# SCH_New-Project_2026-09-16.net
KiCad netlist of a schematic drawn in EasyEDA
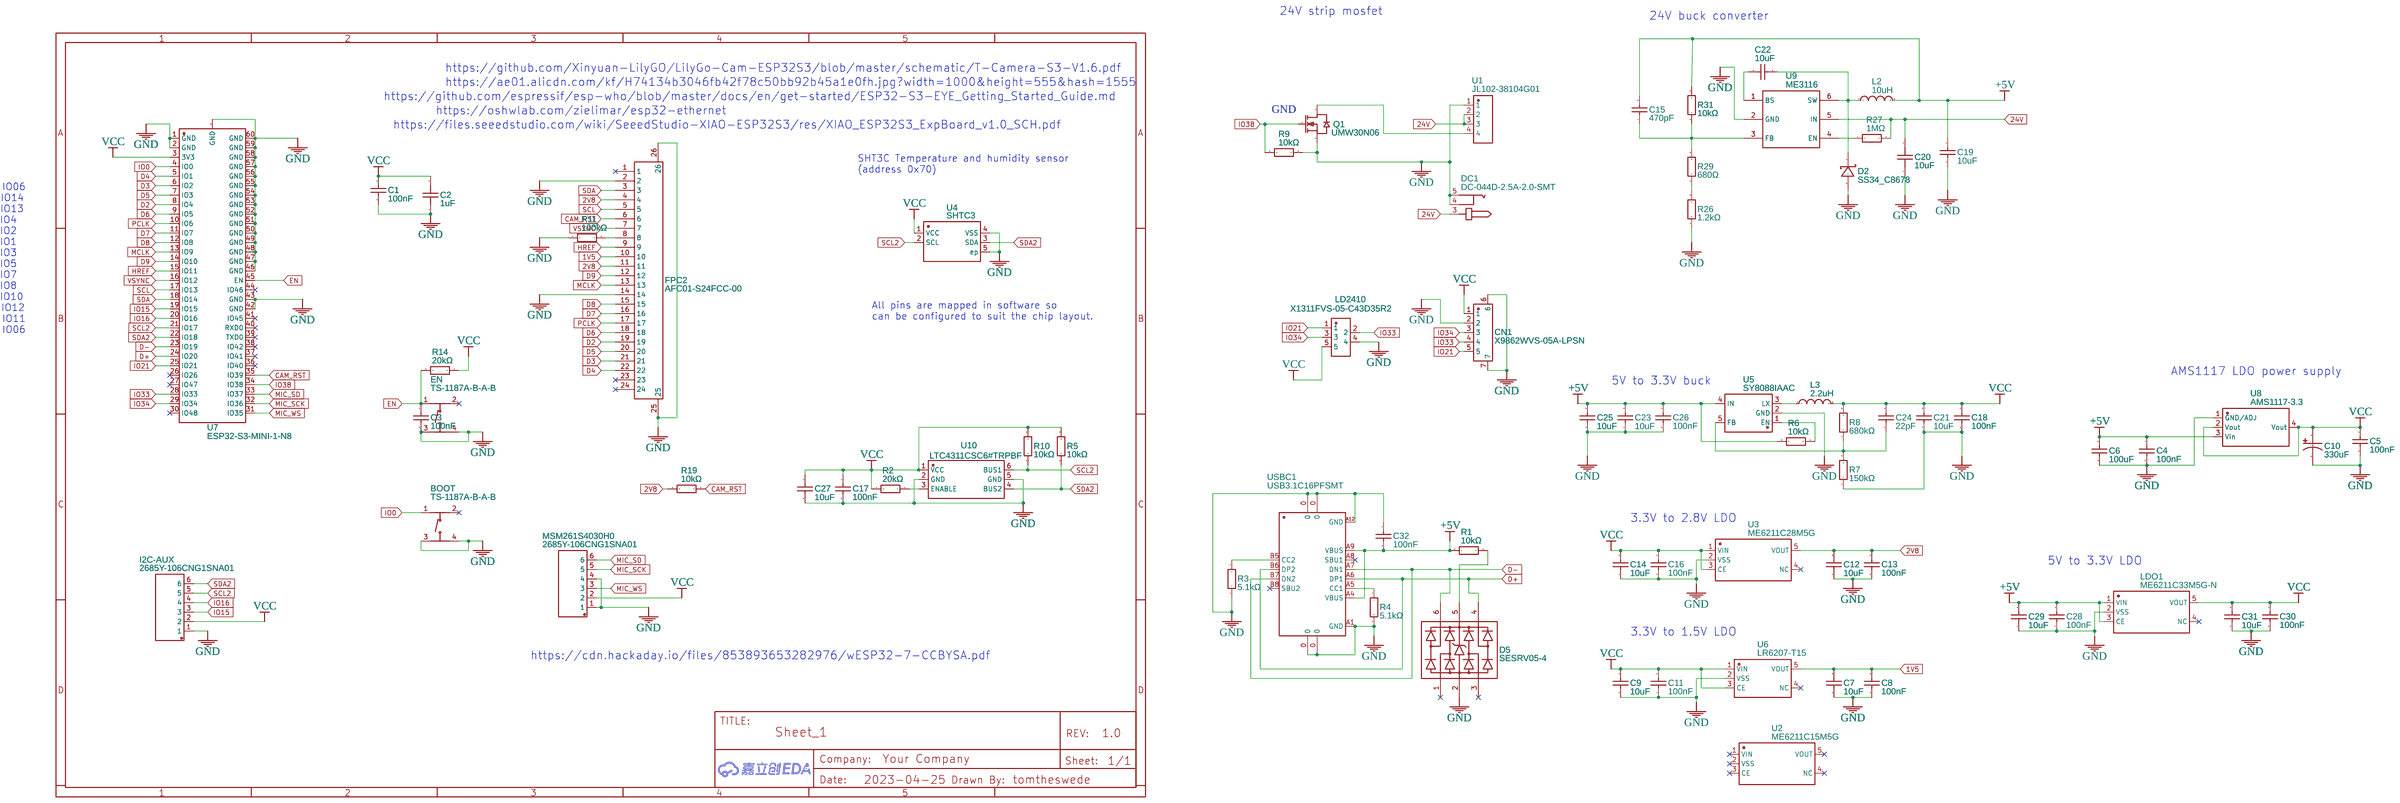
[diagram p0: schematic sheet]

(export (version "E")
  (design (tool "Eeschema 10.0.6"))
  (components
    (comp (ref "BOOT")
      (value "TS-1187A-B-A-B")
      (fields (field (name "Manufacturer") "XKB Enterprise"))
      (libsource (lib "") (part "TS-1187A-B-A-B_1"))
    )
    (comp (ref "C1")
      (value "100nF")
      (fields
        (field (name "Manufacturer Part") "CL05B104KO5NNNC")
        (field (name "Manufacturer") "SAMSUNG(三星)")
      )
      (libsource (lib "") (part "CL05B104KO5NNNC"))
    )
    (comp (ref "C2")
      (value "1uF")
      (fields
        (field (name "Manufacturer Part") "CL05A105KA5NQNC")
        (field (name "Manufacturer") "SAMSUNG(三星)")
      )
      (libsource (lib "") (part "CL05A105KA5NQNC"))
    )
    (comp (ref "C3")
      (value "100nF")
      (fields
        (field (name "Manufacturer Part") "CL05B104KO5NNNC")
        (field (name "Manufacturer") "SAMSUNG(三星)")
      )
      (libsource (lib "") (part "CL05B104KO5NNNC"))
    )
    (comp (ref "C4")
      (value "100nF")
      (fields
        (field (name "Manufacturer Part") "CL05B104KO5NNNC")
        (field (name "Manufacturer") "SAMSUNG(三星)")
      )
      (libsource (lib "") (part "CL05B104KO5NNNC"))
    )
    (comp (ref "C5")
      (value "100nF")
      (fields
        (field (name "Manufacturer Part") "CL05B104KO5NNNC")
        (field (name "Manufacturer") "SAMSUNG(三星)")
      )
      (libsource (lib "") (part "CL05B104KO5NNNC"))
    )
    (comp (ref "C6")
      (value "100uF")
      (fields (field (name "Manufacturer Part") "CL31A107MQHNNNE") (field (name "Manufacturer") "SAMSUNG"))
      (libsource (lib "") (part "CL31A107MQHNNNE"))
    )
    (comp (ref "C7")
      (value "10uF")
      (fields (field (name "Manufacturer Part") "CL05A106MQ5NUNC") (field (name "Manufacturer") "SAMSUNG"))
      (libsource (lib "") (part "CL05A106MQ5NUNC"))
    )
    (comp (ref "C8")
      (value "100nF")
      (fields
        (field (name "Manufacturer Part") "CL05B104KO5NNNC")
        (field (name "Manufacturer") "SAMSUNG(三星)")
      )
      (libsource (lib "") (part "CL05B104KO5NNNC"))
    )
    (comp (ref "C9")
      (value "10uF")
      (fields (field (name "Manufacturer Part") "CL05A106MQ5NUNC") (field (name "Manufacturer") "SAMSUNG"))
      (libsource (lib "") (part "CL05A106MQ5NUNC"))
    )
    (comp (ref "C10")
      (value "330uF")
      (fields
        (field (name "Manufacturer Part") "CA45-C6R3K337T")
        (field (name "Manufacturer") "Hunan Xiangyee in S&T")
      )
      (libsource (lib "") (part "CA45-C6R3K337T"))
    )
    (comp (ref "C11")
      (value "100nF")
      (fields
        (field (name "Manufacturer Part") "CL05B104KO5NNNC")
        (field (name "Manufacturer") "SAMSUNG(三星)")
      )
      (libsource (lib "") (part "CL05B104KO5NNNC"))
    )
    (comp (ref "C12")
      (value "10uF")
      (fields (field (name "Manufacturer Part") "CL05A106MQ5NUNC") (field (name "Manufacturer") "SAMSUNG"))
      (libsource (lib "") (part "CL05A106MQ5NUNC"))
    )
    (comp (ref "C13")
      (value "100nF")
      (fields
        (field (name "Manufacturer Part") "CL05B104KO5NNNC")
        (field (name "Manufacturer") "SAMSUNG(三星)")
      )
      (libsource (lib "") (part "CL05B104KO5NNNC"))
    )
    (comp (ref "C14")
      (value "10uF")
      (fields (field (name "Manufacturer Part") "CL05A106MQ5NUNC") (field (name "Manufacturer") "SAMSUNG"))
      (libsource (lib "") (part "CL05A106MQ5NUNC"))
    )
    (comp (ref "C15")
      (value "470pF")
      (fields (field (name "Manufacturer Part") "0402B471K500NT") (field (name "Manufacturer") "FH(风华)"))
      (libsource (lib "") (part "0402B471K500NT"))
    )
    (comp (ref "C16")
      (value "100nF")
      (fields
        (field (name "Manufacturer Part") "CL05B104KO5NNNC")
        (field (name "Manufacturer") "SAMSUNG(三星)")
      )
      (libsource (lib "") (part "CL05B104KO5NNNC"))
    )
    (comp (ref "C17")
      (value "100nF")
      (fields
        (field (name "Manufacturer Part") "CL05B104KO5NNNC")
        (field (name "Manufacturer") "SAMSUNG(三星)")
      )
      (libsource (lib "") (part "CL05B104KO5NNNC"))
    )
    (comp (ref "C18")
      (value "100nF")
      (fields
        (field (name "Manufacturer Part") "CL05B104KO5NNNC")
        (field (name "Manufacturer") "SAMSUNG(三星)")
      )
      (libsource (lib "") (part "CL05B104KO5NNNC"))
    )
    (comp (ref "C19")
      (value "10uF")
      (fields
        (field (name "Manufacturer Part") "CL21A106KAYNNNE")
        (field (name "Manufacturer") "SAMSUNG(三星)")
      )
      (libsource (lib "") (part "CL21A106KAYNNNE"))
    )
    (comp (ref "C20")
      (value "10uF")
      (fields
        (field (name "Manufacturer Part") "GRM21BR61H106KE43L")
        (field (name "Manufacturer") "muRata(村田)")
      )
      (libsource (lib "") (part "GRM21BR61H106KE43L"))
    )
    (comp (ref "C21")
      (value "10uF")
      (fields (field (name "Manufacturer Part") "CL05A106MQ5NUNC") (field (name "Manufacturer") "SAMSUNG"))
      (libsource (lib "") (part "CL05A106MQ5NUNC"))
    )
    (comp (ref "C22")
      (value "10uF")
      (fields
        (field (name "Manufacturer Part") "CL21A106KAYNNNE")
        (field (name "Manufacturer") "SAMSUNG(三星)")
      )
      (libsource (lib "") (part "CL21A106KAYNNNE_1"))
    )
    (comp (ref "C23")
      (value "10uF")
      (fields (field (name "Manufacturer Part") "CL05A106MQ5NUNC") (field (name "Manufacturer") "SAMSUNG"))
      (libsource (lib "") (part "CL05A106MQ5NUNC"))
    )
    (comp (ref "C24")
      (value "22pF")
      (fields (field (name "Manufacturer Part") "0402CG220J500NT") (field (name "Manufacturer") "FH(风华)"))
      (libsource (lib "") (part "0402CG220J500NT"))
    )
    (comp (ref "C25")
      (value "10uF")
      (fields (field (name "Manufacturer Part") "CL05A106MQ5NUNC") (field (name "Manufacturer") "SAMSUNG"))
      (libsource (lib "") (part "CL05A106MQ5NUNC"))
    )
    (comp (ref "C26")
      (value "100nF")
      (fields
        (field (name "Manufacturer Part") "CL05B104KO5NNNC")
        (field (name "Manufacturer") "SAMSUNG(三星)")
      )
      (libsource (lib "") (part "CL05B104KO5NNNC"))
    )
    (comp (ref "C27")
      (value "10uF")
      (fields (field (name "Manufacturer Part") "CL05A106MQ5NUNC") (field (name "Manufacturer") "SAMSUNG"))
      (libsource (lib "") (part "CL05A106MQ5NUNC"))
    )
    (comp (ref "C28")
      (value "100nF")
      (fields
        (field (name "Manufacturer Part") "CL05B104KO5NNNC")
        (field (name "Manufacturer") "SAMSUNG(三星)")
      )
      (libsource (lib "") (part "CL05B104KO5NNNC"))
    )
    (comp (ref "C29")
      (value "10uF")
      (fields (field (name "Manufacturer Part") "CL05A106MQ5NUNC") (field (name "Manufacturer") "SAMSUNG"))
      (libsource (lib "") (part "CL05A106MQ5NUNC"))
    )
    (comp (ref "C30")
      (value "100nF")
      (fields
        (field (name "Manufacturer Part") "CL05B104KO5NNNC")
        (field (name "Manufacturer") "SAMSUNG(三星)")
      )
      (libsource (lib "") (part "CL05B104KO5NNNC"))
    )
    (comp (ref "C31")
      (value "10uF")
      (fields (field (name "Manufacturer Part") "CL05A106MQ5NUNC") (field (name "Manufacturer") "SAMSUNG"))
      (libsource (lib "") (part "CL05A106MQ5NUNC"))
    )
    (comp (ref "C32")
      (value "100nF")
      (fields
        (field (name "Manufacturer Part") "CL05B104KO5NNNC")
        (field (name "Manufacturer") "SAMSUNG(三星)")
      )
      (libsource (lib "") (part "CL05B104KO5NNNC"))
    )
    (comp (ref "CN1")
      (value "X9862WVS-05A-LPSN")
      (fields
        (field (name "Manufacturer Part") "X9862WVS-05A-6TSN")
        (field (name "Manufacturer") "XKB Connectivity(中国星坤)")
      )
      (libsource (lib "") (part "X9862WVS-05A-LPSN"))
    )
    (comp (ref "D2")
      (value "SS34_C8678")
      (fields (field (name "Manufacturer Part") "SS34") (field (name "Manufacturer") "MDD"))
      (libsource (lib "") (part "SS34_C8678"))
    )
    (comp (ref "D5")
      (value "SESRV05-4")
      (fields (field (name "Manufacturer") "SEMIWARE(赛米微尔)"))
      (libsource (lib "") (part "SESRV05-4"))
    )
    (comp (ref "DC1")
      (value "DC-044D-2.5A-2.0-SMT")
      (fields (field (name "Manufacturer") "XKB Connectivity(中国星坤)"))
      (libsource (lib "") (part "DC-044D-2.5A-2.0-SMT"))
    )
    (comp (ref "EN")
      (value "TS-1187A-B-A-B")
      (fields (field (name "Manufacturer") "XKB Enterprise"))
      (libsource (lib "") (part "TS-1187A-B-A-B"))
    )
    (comp (ref "FPC2")
      (value "AFC01-S24FCC-00")
      (fields (field (name "Manufacturer") "JS(钜硕电子)"))
      (libsource (lib "") (part "AFC01-S24FCC-00"))
    )
    (comp (ref "I2C-AUX")
      (value "2685Y-106CNG1SNA01")
      (fields (field (name "Manufacturer") "华宇创"))
      (libsource (lib "") (part "2685Y-106CNG1SNA01_1"))
    )
    (comp (ref "L2")
      (value "10uH")
      (fields (field (name "Manufacturer Part") "SM5845-100MT") (field (name "Manufacturer") "SXN(顺翔诺)"))
      (libsource (lib "") (part "SM5845-100MT"))
    )
    (comp (ref "L3")
      (value "2.2uH")
      (fields (field (name "Manufacturer Part") "FNR4030S2R2MT") (field (name "Manufacturer") "cjiang(长江微电)"))
      (libsource (lib "") (part "FNR4030S2R2MT"))
    )
    (comp (ref "LD2410")
      (value "X1311FVS-05-C43D35R2")
      (fields (field (name "Manufacturer") "XKB Connectivity(中国星坤)"))
      (libsource (lib "") (part "X1311FVS-05-C43D35R2"))
    )
    (comp (ref "LDO1")
      (value "ME6211C33M5G-N")
      (fields (field (name "Manufacturer") "MICRONE(南京微盟)"))
      (libsource (lib "") (part "ME6211C33M5G-N"))
    )
    (comp (ref "MSM261S4030H0")
      (value "2685Y-106CNG1SNA01")
      (fields (field (name "Manufacturer") "华宇创"))
      (libsource (lib "") (part "2685Y-106CNG1SNA01"))
    )
    (comp (ref "Q1")
      (value "UMW30N06")
      (fields (field (name "Manufacturer Part") "30N06") (field (name "Manufacturer") "UMW(广东友台半导体)"))
      (libsource (lib "") (part "UMW30N06"))
    )
    (comp (ref "R1")
      (value "10kΩ")
      (fields (field (name "Manufacturer Part") "0402WGF1002TCE") (field (name "Manufacturer") "UniOhm"))
      (libsource (lib "") (part "0402WGF1002TCE"))
    )
    (comp (ref "R2")
      (value "20kΩ")
      (fields
        (field (name "Manufacturer Part") "0402WGF2002TCE")
        (field (name "Manufacturer") "UNI-ROYAL(厚声)")
      )
      (libsource (lib "") (part "0402WGF2002TCE"))
    )
    (comp (ref "R3")
      (value "5.1kΩ")
      (fields (field (name "Manufacturer Part") "0402WGF5101TCE") (field (name "Manufacturer") "UniOhm"))
      (libsource (lib "") (part "0402WGF5101TCE"))
    )
    (comp (ref "R4")
      (value "5.1kΩ")
      (fields (field (name "Manufacturer Part") "0402WGF5101TCE") (field (name "Manufacturer") "UniOhm"))
      (libsource (lib "") (part "0402WGF5101TCE_1"))
    )
    (comp (ref "R5")
      (value "10kΩ")
      (fields (field (name "Manufacturer Part") "0402WGF1002TCE") (field (name "Manufacturer") "UniOhm"))
      (libsource (lib "") (part "0402WGF1002TCE_1"))
    )
    (comp (ref "R6")
      (value "10kΩ")
      (fields (field (name "Manufacturer Part") "0402WGF1002TCE") (field (name "Manufacturer") "UniOhm"))
      (libsource (lib "") (part "0402WGF1002TCE"))
    )
    (comp (ref "R7")
      (value "150kΩ")
      (fields
        (field (name "Manufacturer Part") "0402WGF1503TCE")
        (field (name "Manufacturer") "UNI-ROYAL(厚声)")
      )
      (libsource (lib "") (part "0402WGF1503TCE"))
    )
    (comp (ref "R8")
      (value "680kΩ")
      (fields
        (field (name "Manufacturer Part") "0603WAF6803T5E")
        (field (name "Manufacturer") "UNI-ROYAL(厚声)")
      )
      (libsource (lib "") (part "0603WAF6803T5E"))
    )
    (comp (ref "R9")
      (value "10kΩ")
      (fields (field (name "Manufacturer Part") "0402WGF1002TCE") (field (name "Manufacturer") "UniOhm"))
      (libsource (lib "") (part "0402WGF1002TCE_2"))
    )
    (comp (ref "R10")
      (value "10kΩ")
      (fields (field (name "Manufacturer Part") "0402WGF1002TCE") (field (name "Manufacturer") "UniOhm"))
      (libsource (lib "") (part "0402WGF1002TCE_1"))
    )
    (comp (ref "R11")
      (value "100kΩ")
      (fields
        (field (name "Manufacturer Part") "0402WGF1003TCE")
        (field (name "Manufacturer") "UNI-ROYAL(厚声)")
      )
      (libsource (lib "") (part "0402WGF1003TCE"))
    )
    (comp (ref "R14")
      (value "20kΩ")
      (fields
        (field (name "Manufacturer Part") "0402WGF2002TCE")
        (field (name "Manufacturer") "UNI-ROYAL(厚声)")
      )
      (libsource (lib "") (part "0402WGF2002TCE"))
    )
    (comp (ref "R19")
      (value "10kΩ")
      (fields (field (name "Manufacturer Part") "0402WGF1002TCE") (field (name "Manufacturer") "UniOhm"))
      (libsource (lib "") (part "0402WGF1002TCE_2"))
    )
    (comp (ref "R26")
      (value "1.2kΩ")
      (fields
        (field (name "Manufacturer Part") "0402WGF1201TCE")
        (field (name "Manufacturer") "UNI-ROYAL(厚声)")
      )
      (libsource (lib "") (part "0402WGF1201TCE"))
    )
    (comp (ref "R27")
      (value "1MΩ")
      (fields
        (field (name "Manufacturer Part") "0805W8F1004T5E")
        (field (name "Manufacturer") "UNI-ROYAL(厚声)")
      )
      (libsource (lib "") (part "0805W8F1004T5E"))
    )
    (comp (ref "R29")
      (value "680Ω")
      (fields
        (field (name "Manufacturer Part") "0402WGF6800TCE")
        (field (name "Manufacturer") "UNI-ROYAL(厚声)")
      )
      (libsource (lib "") (part "0402WGF6800TCE"))
    )
    (comp (ref "R31")
      (value "10kΩ")
      (fields (field (name "Manufacturer Part") "0402WGF1002TCE") (field (name "Manufacturer") "UniOhm"))
      (libsource (lib "") (part "0402WGF1002TCE_1"))
    )
    (comp (ref "U1")
      (value "JL102-38104G01")
      (fields (field (name "Manufacturer") "JILN(锦凌)"))
      (libsource (lib "") (part "JL102-38104G01"))
    )
    (comp (ref "U2")
      (value "ME6211C15M5G")
      (fields
        (field (name "Manufacturer Part") "ME6211C15M5G-N")
        (field (name "Manufacturer") "MICRONE(南京微盟)")
      )
      (libsource (lib "") (part "ME6211C15M5G"))
    )
    (comp (ref "U3")
      (value "ME6211C28M5G")
      (fields
        (field (name "Manufacturer Part") "ME6211C28M5G-N")
        (field (name "Manufacturer") "MICRONE(南京微盟)")
      )
      (libsource (lib "") (part "ME6211C28M5G"))
    )
    (comp (ref "U4")
      (value "SHTC3")
      (fields (field (name "Manufacturer") "Sensirion"))
      (libsource (lib "") (part "SHTC3"))
    )
    (comp (ref "U5")
      (value "SY8088IAAC")
      (fields (field (name "Manufacturer") "矽力杰silergy"))
      (libsource (lib "") (part "SY8088IAAC"))
    )
    (comp (ref "U6")
      (value "LR6207-T15")
      (fields (field (name "Manufacturer") "LR(朗瑞)"))
      (libsource (lib "") (part "LR6207-T15"))
    )
    (comp (ref "U7")
      (value "ESP32-S3-MINI-1-N8")
      (fields (field (name "Manufacturer") "ESPRESSIF(乐鑫)"))
      (libsource (lib "") (part "ESP32-S3-MINI-1-N8"))
    )
    (comp (ref "U8")
      (value "AMS1117-3.3")
      (fields (field (name "Manufacturer") "AMS"))
      (libsource (lib "") (part "AMS1117-3.3"))
    )
    (comp (ref "U9")
      (value "ME3116")
      (fields (field (name "Manufacturer Part") "ME3116AM6G") (field (name "Manufacturer") "MICRONE(南京微盟)"))
      (libsource (lib "") (part "ME3116"))
    )
    (comp (ref "U10")
      (value "LTC4311CSC6#TRPBF")
      (fields (field (name "Manufacturer") "ADI(亚德诺)"))
      (libsource (lib "") (part "LTC4311CSC6#TRPBF"))
    )
    (comp (ref "USBC1")
      (value "USB3.1C16PFSMT")
      (fields (field (name "Manufacturer") "LCSC"))
      (libsource (lib "") (part "USB3.1C16PFSMT"))
    )
  )
  (nets
    (net (code "1") (name "+5V") (class "Default")
      (node (ref "C15") (pin "2") (pinfunction "2_2") (pintype "input"))
      (node (ref "C19") (pin "2") (pinfunction "2_2") (pintype "input"))
      (node (ref "C23") (pin "2") (pinfunction "2_2") (pintype "input"))
      (node (ref "C25") (pin "2") (pinfunction "2_2") (pintype "input"))
      (node (ref "C26") (pin "1") (pinfunction "1_1") (pintype "input"))
      (node (ref "C28") (pin "1") (pinfunction "1_1") (pintype "input"))
      (node (ref "C29") (pin "2") (pinfunction "2_2") (pintype "input"))
      (node (ref "C32") (pin "2") (pinfunction "2_2") (pintype "input"))
      (node (ref "C4") (pin "1") (pinfunction "1_1") (pintype "input"))
      (node (ref "C6") (pin "1") (pinfunction "1_1") (pintype "input"))
      (node (ref "L2") (pin "2") (pinfunction "2_2") (pintype "unspecified"))
      (node (ref "LDO1") (pin "1") (pinfunction "VIN_1") (pintype "unspecified"))
      (node (ref "LDO1") (pin "3") (pinfunction "CE_3") (pintype "unspecified"))
      (node (ref "R1") (pin "2") (pinfunction "2_2") (pintype "input"))
      (node (ref "R31") (pin "2") (pinfunction "2_2") (pintype "input"))
      (node (ref "R6") (pin "2") (pinfunction "2_2") (pintype "input"))
      (node (ref "U5") (pin "4") (pinfunction "IN_4") (pintype "unspecified"))
      (node (ref "U8") (pin "3") (pinfunction "Vin_3") (pintype "unspecified"))
      (node (ref "USBC1") (pin "A4") (pinfunction "VBUS_A4") (pintype "unspecified"))
      (node (ref "USBC1") (pin "A9") (pinfunction "VBUS_A9") (pintype "unspecified"))
    )
    (net (code "2") (name "1V5") (class "Default")
      (node (ref "C7") (pin "2") (pinfunction "2_2") (pintype "input"))
      (node (ref "C8") (pin "1") (pinfunction "1_1") (pintype "input"))
      (node (ref "FPC2") (pin "10") (pinfunction "10_10") (pintype "unspecified"))
      (node (ref "U6") (pin "5") (pinfunction "VOUT_5") (pintype "unspecified"))
    )
    (net (code "3") (name "2V8") (class "Default")
      (node (ref "C12") (pin "2") (pinfunction "2_2") (pintype "input"))
      (node (ref "C13") (pin "1") (pinfunction "1_1") (pintype "input"))
      (node (ref "FPC2") (pin "11") (pinfunction "11_11") (pintype "unspecified"))
      (node (ref "FPC2") (pin "4") (pinfunction "4_4") (pintype "unspecified"))
      (node (ref "R19") (pin "1") (pinfunction "1_1") (pintype "input"))
      (node (ref "U3") (pin "5") (pinfunction "VOUT_5") (pintype "unspecified"))
    )
    (net (code "4") (name "24V") (class "Default")
      (node (ref "C20") (pin "2") (pinfunction "2_2") (pintype "unspecified"))
      (node (ref "DC1") (pin "3") (pinfunction "3_3") (pintype "unspecified"))
      (node (ref "R27") (pin "2") (pinfunction "2_2") (pintype "input"))
      (node (ref "U1") (pin "2") (pinfunction "2_2") (pintype "unspecified"))
      (node (ref "U1") (pin "3") (pinfunction "3_3") (pintype "unspecified"))
      (node (ref "U9") (pin "5") (pinfunction "IN_5") (pintype "unspecified"))
    )
    (net (code "5") (name "CAM_RST") (class "Default")
      (node (ref "FPC2") (pin "6") (pinfunction "6_6") (pintype "unspecified"))
      (node (ref "R19") (pin "2") (pinfunction "2_2") (pintype "input"))
      (node (ref "U7") (pin "35") (pinfunction "IO39_35") (pintype "unspecified"))
    )
    (net (code "6") (name "D+") (class "Default")
      (node (ref "D5") (pin "4") (pinfunction "4_4") (pintype "unspecified"))
      (node (ref "U7") (pin "24") (pinfunction "IO20_24") (pintype "unspecified"))
      (node (ref "USBC1") (pin "A6") (pinfunction "DP1_A6") (pintype "unspecified"))
      (node (ref "USBC1") (pin "B6") (pinfunction "DP2_B6") (pintype "unspecified"))
    )
    (net (code "7") (name "D-") (class "Default")
      (node (ref "D5") (pin "6") (pinfunction "6_6") (pintype "unspecified"))
      (node (ref "U7") (pin "23") (pinfunction "IO19_23") (pintype "unspecified"))
      (node (ref "USBC1") (pin "A7") (pinfunction "DN1_A7") (pintype "unspecified"))
      (node (ref "USBC1") (pin "B7") (pinfunction "DN2_B7") (pintype "unspecified"))
    )
    (net (code "8") (name "D2") (class "Default")
      (node (ref "FPC2") (pin "19") (pinfunction "19_19") (pintype "unspecified"))
      (node (ref "U7") (pin "8") (pinfunction "IO4_8") (pintype "unspecified"))
    )
    (net (code "9") (name "D3") (class "Default")
      (node (ref "FPC2") (pin "21") (pinfunction "21_21") (pintype "unspecified"))
      (node (ref "U7") (pin "6") (pinfunction "IO2_6") (pintype "unspecified"))
    )
    (net (code "10") (name "D4") (class "Default")
      (node (ref "FPC2") (pin "22") (pinfunction "22_22") (pintype "unspecified"))
      (node (ref "U7") (pin "5") (pinfunction "IO1_5") (pintype "unspecified"))
    )
    (net (code "11") (name "D5") (class "Default")
      (node (ref "FPC2") (pin "20") (pinfunction "20_20") (pintype "unspecified"))
      (node (ref "U7") (pin "7") (pinfunction "IO3_7") (pintype "unspecified"))
    )
    (net (code "12") (name "D6") (class "Default")
      (node (ref "FPC2") (pin "18") (pinfunction "18_18") (pintype "unspecified"))
      (node (ref "U7") (pin "9") (pinfunction "IO5_9") (pintype "unspecified"))
    )
    (net (code "13") (name "D7") (class "Default")
      (node (ref "FPC2") (pin "16") (pinfunction "16_16") (pintype "unspecified"))
      (node (ref "U7") (pin "11") (pinfunction "IO7_11") (pintype "unspecified"))
    )
    (net (code "14") (name "D8") (class "Default")
      (node (ref "FPC2") (pin "15") (pinfunction "15_15") (pintype "unspecified"))
      (node (ref "U7") (pin "12") (pinfunction "IO8_12") (pintype "unspecified"))
    )
    (net (code "15") (name "D9") (class "Default")
      (node (ref "FPC2") (pin "12") (pinfunction "12_12") (pintype "unspecified"))
      (node (ref "U7") (pin "14") (pinfunction "IO10_14") (pintype "unspecified"))
    )
    (net (code "16") (name "EN") (class "Default")
      (node (ref "C3") (pin "1") (pinfunction "1_1") (pintype "input"))
      (node (ref "EN") (pin "1") (pinfunction "A_1") (pintype "unspecified"))
      (node (ref "R14") (pin "2") (pinfunction "2_2") (pintype "input"))
      (node (ref "U7") (pin "45") (pinfunction "EN_45") (pintype "unspecified"))
    )
    (net (code "17") (name "GND") (class "Default")
      (node (ref "BOOT") (pin "3") (pinfunction "C_3") (pintype "unspecified"))
      (node (ref "BOOT") (pin "4") (pinfunction "D_4") (pintype "unspecified"))
      (node (ref "C1") (pin "2") (pinfunction "2_2") (pintype "input"))
      (node (ref "C10") (pin "2") (pinfunction "2_2") (pintype "unspecified"))
      (node (ref "C11") (pin "2") (pinfunction "2_2") (pintype "input"))
      (node (ref "C12") (pin "1") (pinfunction "1_1") (pintype "input"))
      (node (ref "C13") (pin "2") (pinfunction "2_2") (pintype "input"))
      (node (ref "C14") (pin "1") (pinfunction "1_1") (pintype "input"))
      (node (ref "C16") (pin "2") (pinfunction "2_2") (pintype "input"))
      (node (ref "C17") (pin "2") (pinfunction "2_2") (pintype "input"))
      (node (ref "C18") (pin "2") (pinfunction "2_2") (pintype "input"))
      (node (ref "C19") (pin "1") (pinfunction "1_1") (pintype "input"))
      (node (ref "C2") (pin "1") (pinfunction "1_1") (pintype "unspecified"))
      (node (ref "C20") (pin "1") (pinfunction "1_1") (pintype "unspecified"))
      (node (ref "C21") (pin "1") (pinfunction "1_1") (pintype "input"))
      (node (ref "C23") (pin "1") (pinfunction "1_1") (pintype "input"))
      (node (ref "C25") (pin "1") (pinfunction "1_1") (pintype "input"))
      (node (ref "C26") (pin "2") (pinfunction "2_2") (pintype "input"))
      (node (ref "C27") (pin "1") (pinfunction "1_1") (pintype "input"))
      (node (ref "C28") (pin "2") (pinfunction "2_2") (pintype "input"))
      (node (ref "C29") (pin "1") (pinfunction "1_1") (pintype "input"))
      (node (ref "C3") (pin "2") (pinfunction "2_2") (pintype "input"))
      (node (ref "C30") (pin "2") (pinfunction "2_2") (pintype "input"))
      (node (ref "C31") (pin "1") (pinfunction "1_1") (pintype "input"))
      (node (ref "C32") (pin "1") (pinfunction "1_1") (pintype "input"))
      (node (ref "C4") (pin "2") (pinfunction "2_2") (pintype "input"))
      (node (ref "C5") (pin "2") (pinfunction "2_2") (pintype "input"))
      (node (ref "C6") (pin "2") (pinfunction "2_2") (pintype "input"))
      (node (ref "C7") (pin "1") (pinfunction "1_1") (pintype "input"))
      (node (ref "C8") (pin "2") (pinfunction "2_2") (pintype "input"))
      (node (ref "C9") (pin "1") (pinfunction "1_1") (pintype "input"))
      (node (ref "CN1") (pin "2") (pinfunction "2_2") (pintype "unspecified"))
      (node (ref "CN1") (pin "6") (pinfunction "6_6") (pintype "unspecified"))
      (node (ref "CN1") (pin "7") (pinfunction "7_7") (pintype "unspecified"))
      (node (ref "D2") (pin "2") (pinfunction "A_2") (pintype "unspecified"))
      (node (ref "D5") (pin "2") (pinfunction "2_2") (pintype "unspecified"))
      (node (ref "DC1") (pin "4") (pinfunction "4_4") (pintype "unspecified"))
      (node (ref "DC1") (pin "5") (pinfunction "5_5") (pintype "unspecified"))
      (node (ref "EN") (pin "3") (pinfunction "C_3") (pintype "unspecified"))
      (node (ref "EN") (pin "4") (pinfunction "D_4") (pintype "unspecified"))
      (node (ref "FPC2") (pin "14") (pinfunction "14_14") (pintype "unspecified"))
      (node (ref "FPC2") (pin "2") (pinfunction "2_2") (pintype "unspecified"))
      (node (ref "FPC2") (pin "25") (pinfunction "25_25") (pintype "unspecified"))
      (node (ref "FPC2") (pin "26") (pinfunction "26_26") (pintype "unspecified"))
      (node (ref "I2C-AUX") (pin "1") (pinfunction "1_1") (pintype "unspecified"))
      (node (ref "LD2410") (pin "4") (pinfunction "4_4") (pintype "unspecified"))
      (node (ref "LDO1") (pin "2") (pinfunction "VSS_2") (pintype "unspecified"))
      (node (ref "MSM261S4030H0") (pin "1") (pinfunction "1_1") (pintype "unspecified"))
      (node (ref "MSM261S4030H0") (pin "4") (pinfunction "4_4") (pintype "unspecified"))
      (node (ref "Q1") (pin "3") (pinfunction "S_3") (pintype "unspecified"))
      (node (ref "R11") (pin "1") (pinfunction "1_1") (pintype "input"))
      (node (ref "R26") (pin "1") (pinfunction "1_1") (pintype "input"))
      (node (ref "R3") (pin "1") (pinfunction "1_1") (pintype "input"))
      (node (ref "R4") (pin "2") (pinfunction "2_2") (pintype "input"))
      (node (ref "R7") (pin "1") (pinfunction "1_1") (pintype "input"))
      (node (ref "R9") (pin "2") (pinfunction "2_2") (pintype "input"))
      (node (ref "U1") (pin "1") (pinfunction "1_1") (pintype "unspecified"))
      (node (ref "U10") (pin "2") (pinfunction "GND_2") (pintype "unspecified"))
      (node (ref "U10") (pin "5") (pinfunction "GND_5") (pintype "unspecified"))
      (node (ref "U3") (pin "2") (pinfunction "VSS_2") (pintype "unspecified"))
      (node (ref "U4") (pin "4") (pinfunction "VSS_4") (pintype "unspecified"))
      (node (ref "U4") (pin "5") (pinfunction "ep_5") (pintype "unspecified"))
      (node (ref "U5") (pin "2") (pinfunction "GND_2") (pintype "unspecified"))
      (node (ref "U6") (pin "2") (pinfunction "VSS_2") (pintype "unspecified"))
      (node (ref "U7") (pin "1") (pinfunction "GND_1") (pintype "unspecified"))
      (node (ref "U7") (pin "2") (pinfunction "GND_2") (pintype "unspecified"))
      (node (ref "U7") (pin "42") (pinfunction "GND_42") (pintype "unspecified"))
      (node (ref "U7") (pin "43") (pinfunction "GND_43") (pintype "unspecified"))
      (node (ref "U7") (pin "46") (pinfunction "GND_46") (pintype "unspecified"))
      (node (ref "U7") (pin "47") (pinfunction "GND_47") (pintype "unspecified"))
      (node (ref "U7") (pin "48") (pinfunction "GND_48") (pintype "unspecified"))
      (node (ref "U7") (pin "49") (pinfunction "GND_49") (pintype "unspecified"))
      (node (ref "U7") (pin "50") (pinfunction "GND_50") (pintype "unspecified"))
      (node (ref "U7") (pin "51") (pinfunction "GND_51") (pintype "unspecified"))
      (node (ref "U7") (pin "52") (pinfunction "GND_52") (pintype "unspecified"))
      (node (ref "U7") (pin "53") (pinfunction "GND_53") (pintype "unspecified"))
      (node (ref "U7") (pin "54") (pinfunction "GND_54") (pintype "unspecified"))
      (node (ref "U7") (pin "55") (pinfunction "GND_55") (pintype "unspecified"))
      (node (ref "U7") (pin "56") (pinfunction "GND_56") (pintype "unspecified"))
      (node (ref "U7") (pin "57") (pinfunction "GND_57") (pintype "unspecified"))
      (node (ref "U7") (pin "58") (pinfunction "GND_58") (pintype "unspecified"))
      (node (ref "U7") (pin "59") (pinfunction "GND_59") (pintype "unspecified"))
      (node (ref "U7") (pin "60") (pinfunction "GND_60") (pintype "unspecified"))
      (node (ref "U7") (pin "GND") (pinfunction "GND_GND") (pintype "unspecified"))
      (node (ref "U8") (pin "1") (pinfunction "GND/ADJ_1") (pintype "unspecified"))
      (node (ref "U9") (pin "2") (pinfunction "GND_2") (pintype "unspecified"))
      (node (ref "USBC1") (pin "0") (pinfunction "0_0") (pintype "unspecified"))
      (node (ref "USBC1") (pin "A1") (pinfunction "GND_A1") (pintype "unspecified"))
      (node (ref "USBC1") (pin "A12") (pinfunction "GND_A12") (pintype "unspecified"))
    )
    (net (code "18") (name "HREF") (class "Default")
      (node (ref "FPC2") (pin "9") (pinfunction "9_9") (pintype "unspecified"))
      (node (ref "U7") (pin "15") (pinfunction "IO11_15") (pintype "unspecified"))
    )
    (net (code "19") (name "IO0") (class "Default")
      (node (ref "BOOT") (pin "1") (pinfunction "A_1") (pintype "unspecified"))
      (node (ref "U7") (pin "4") (pinfunction "IO0_4") (pintype "unspecified"))
    )
    (net (code "20") (name "IO15") (class "Default")
      (node (ref "I2C-AUX") (pin "3") (pinfunction "3_3") (pintype "unspecified"))
      (node (ref "U7") (pin "19") (pinfunction "IO15_19") (pintype "unspecified"))
    )
    (net (code "21") (name "IO16") (class "Default")
      (node (ref "I2C-AUX") (pin "4") (pinfunction "4_4") (pintype "unspecified"))
      (node (ref "U7") (pin "20") (pinfunction "IO16_20") (pintype "unspecified"))
    )
    (net (code "22") (name "IO21") (class "Default")
      (node (ref "CN1") (pin "5") (pinfunction "5_5") (pintype "unspecified"))
      (node (ref "LD2410") (pin "1") (pinfunction "1_1") (pintype "unspecified"))
      (node (ref "U7") (pin "25") (pinfunction "IO21_25") (pintype "unspecified"))
    )
    (net (code "23") (name "IO33") (class "Default")
      (node (ref "CN1") (pin "4") (pinfunction "4_4") (pintype "unspecified"))
      (node (ref "LD2410") (pin "2") (pinfunction "2_2") (pintype "unspecified"))
      (node (ref "U7") (pin "28") (pinfunction "IO33_28") (pintype "unspecified"))
    )
    (net (code "24") (name "IO34") (class "Default")
      (node (ref "CN1") (pin "3") (pinfunction "3_3") (pintype "unspecified"))
      (node (ref "LD2410") (pin "3") (pinfunction "3_3") (pintype "unspecified"))
      (node (ref "U7") (pin "29") (pinfunction "IO34_29") (pintype "unspecified"))
    )
    (net (code "25") (name "IO38") (class "Default")
      (node (ref "Q1") (pin "1") (pinfunction "G_1") (pintype "unspecified"))
      (node (ref "R9") (pin "1") (pinfunction "1_1") (pintype "input"))
      (node (ref "U7") (pin "34") (pinfunction "IO38_34") (pintype "unspecified"))
    )
    (net (code "26") (name "MCLK") (class "Default")
      (node (ref "FPC2") (pin "13") (pinfunction "13_13") (pintype "unspecified"))
      (node (ref "U7") (pin "13") (pinfunction "IO9_13") (pintype "unspecified"))
    )
    (net (code "27") (name "MIC_SCK") (class "Default")
      (node (ref "MSM261S4030H0") (pin "5") (pinfunction "5_5") (pintype "unspecified"))
      (node (ref "U7") (pin "32") (pinfunction "IO36_32") (pintype "unspecified"))
    )
    (net (code "28") (name "MIC_SD") (class "Default")
      (node (ref "MSM261S4030H0") (pin "6") (pinfunction "6_6") (pintype "unspecified"))
      (node (ref "U7") (pin "33") (pinfunction "IO37_33") (pintype "unspecified"))
    )
    (net (code "29") (name "MIC_WS") (class "Default")
      (node (ref "MSM261S4030H0") (pin "3") (pinfunction "3_3") (pintype "unspecified"))
      (node (ref "U7") (pin "31") (pinfunction "IO35_31") (pintype "unspecified"))
    )
    (net (code "30") (name "Net-(D2-K)") (class "Default")
      (node (ref "C22") (pin "1") (pinfunction "1_1") (pintype "input"))
      (node (ref "D2") (pin "1") (pinfunction "K_1") (pintype "unspecified"))
      (node (ref "L2") (pin "1") (pinfunction "1_1") (pintype "unspecified"))
      (node (ref "U9") (pin "6") (pinfunction "SW_6") (pintype "unspecified"))
    )
    (net (code "31") (name "Net-(D5-Pad5)") (class "Default")
      (node (ref "D5") (pin "5") (pinfunction "5_5") (pintype "unspecified"))
      (node (ref "R1") (pin "1") (pinfunction "1_1") (pintype "input"))
    )
    (net (code "32") (name "Net-(FPC2-Pad8)") (class "Default")
      (node (ref "FPC2") (pin "8") (pinfunction "8_8") (pintype "unspecified"))
      (node (ref "R11") (pin "2") (pinfunction "2_2") (pintype "input"))
    )
    (net (code "33") (name "Net-(Q1-D)") (class "Default")
      (node (ref "Q1") (pin "2") (pinfunction "D_2") (pintype "unspecified"))
      (node (ref "U1") (pin "4") (pinfunction "4_4") (pintype "unspecified"))
    )
    (net (code "34") (name "Net-(R26-Pad2)") (class "Default")
      (node (ref "R26") (pin "2") (pinfunction "2_2") (pintype "input"))
      (node (ref "R29") (pin "1") (pinfunction "1_1") (pintype "input"))
    )
    (net (code "35") (name "Net-(U5-EN)") (class "Default")
      (node (ref "R6") (pin "1") (pinfunction "1_1") (pintype "input"))
      (node (ref "U5") (pin "1") (pinfunction "EN_1") (pintype "unspecified"))
    )
    (net (code "36") (name "Net-(U5-FB)") (class "Default")
      (node (ref "C24") (pin "1") (pinfunction "1_1") (pintype "input"))
      (node (ref "R7") (pin "2") (pinfunction "2_2") (pintype "input"))
      (node (ref "R8") (pin "1") (pinfunction "1_1") (pintype "input"))
      (node (ref "U5") (pin "5") (pinfunction "FB_5") (pintype "unspecified"))
    )
    (net (code "37") (name "Net-(U5-LX)") (class "Default")
      (node (ref "L3") (pin "1") (pinfunction "1_1") (pintype "unspecified"))
      (node (ref "U5") (pin "3") (pinfunction "LX_3") (pintype "unspecified"))
    )
    (net (code "38") (name "Net-(U9-BS)") (class "Default")
      (node (ref "C22") (pin "2") (pinfunction "2_2") (pintype "input"))
      (node (ref "U9") (pin "1") (pinfunction "BS_1") (pintype "unspecified"))
    )
    (net (code "39") (name "Net-(U9-EN)") (class "Default")
      (node (ref "R27") (pin "1") (pinfunction "1_1") (pintype "input"))
      (node (ref "U9") (pin "4") (pinfunction "EN_4") (pintype "unspecified"))
    )
    (net (code "40") (name "Net-(U9-FB)") (class "Default")
      (node (ref "C15") (pin "1") (pinfunction "1_1") (pintype "input"))
      (node (ref "R29") (pin "2") (pinfunction "2_2") (pintype "input"))
      (node (ref "R31") (pin "1") (pinfunction "1_1") (pintype "input"))
      (node (ref "U9") (pin "3") (pinfunction "FB_3") (pintype "unspecified"))
    )
    (net (code "41") (name "Net-(U10-ENABLE)") (class "Default")
      (node (ref "R2") (pin "1") (pinfunction "1_1") (pintype "input"))
      (node (ref "U10") (pin "3") (pinfunction "ENABLE_3") (pintype "unspecified"))
    )
    (net (code "42") (name "Net-(USBC1-CC1)") (class "Default")
      (node (ref "R4") (pin "1") (pinfunction "1_1") (pintype "input"))
      (node (ref "USBC1") (pin "A5") (pinfunction "CC1_A5") (pintype "unspecified"))
    )
    (net (code "43") (name "Net-(USBC1-CC2)") (class "Default")
      (node (ref "R3") (pin "2") (pinfunction "2_2") (pintype "input"))
      (node (ref "USBC1") (pin "B5") (pinfunction "CC2_B5") (pintype "unspecified"))
    )
    (net (code "44") (name "PCLK") (class "Default")
      (node (ref "FPC2") (pin "17") (pinfunction "17_17") (pintype "unspecified"))
      (node (ref "U7") (pin "10") (pinfunction "IO6_10") (pintype "unspecified"))
    )
    (net (code "45") (name "SCL") (class "Default")
      (node (ref "FPC2") (pin "5") (pinfunction "5_5") (pintype "unspecified"))
      (node (ref "U7") (pin "17") (pinfunction "IO13_17") (pintype "unspecified"))
    )
    (net (code "46") (name "SCL2") (class "Default")
      (node (ref "I2C-AUX") (pin "5") (pinfunction "5_5") (pintype "unspecified"))
      (node (ref "R10") (pin "1") (pinfunction "1_1") (pintype "input"))
      (node (ref "U10") (pin "6") (pinfunction "BUS1_6") (pintype "unspecified"))
      (node (ref "U4") (pin "2") (pinfunction "SCL_2") (pintype "unspecified"))
      (node (ref "U7") (pin "21") (pinfunction "IO17_21") (pintype "unspecified"))
    )
    (net (code "47") (name "SDA") (class "Default")
      (node (ref "FPC2") (pin "3") (pinfunction "3_3") (pintype "unspecified"))
      (node (ref "U7") (pin "18") (pinfunction "IO14_18") (pintype "unspecified"))
    )
    (net (code "48") (name "SDA2") (class "Default")
      (node (ref "I2C-AUX") (pin "6") (pinfunction "6_6") (pintype "unspecified"))
      (node (ref "R5") (pin "1") (pinfunction "1_1") (pintype "input"))
      (node (ref "U10") (pin "4") (pinfunction "BUS2_4") (pintype "unspecified"))
      (node (ref "U4") (pin "3") (pinfunction "SDA_3") (pintype "unspecified"))
      (node (ref "U7") (pin "22") (pinfunction "IO18_22") (pintype "unspecified"))
    )
    (net (code "49") (name "VCC") (class "Default")
      (node (ref "C1") (pin "1") (pinfunction "1_1") (pintype "input"))
      (node (ref "C10") (pin "1") (pinfunction "1_1") (pintype "unspecified"))
      (node (ref "C11") (pin "1") (pinfunction "1_1") (pintype "input"))
      (node (ref "C14") (pin "2") (pinfunction "2_2") (pintype "input"))
      (node (ref "C16") (pin "1") (pinfunction "1_1") (pintype "input"))
      (node (ref "C17") (pin "1") (pinfunction "1_1") (pintype "input"))
      (node (ref "C18") (pin "1") (pinfunction "1_1") (pintype "input"))
      (node (ref "C2") (pin "2") (pinfunction "2_2") (pintype "unspecified"))
      (node (ref "C21") (pin "2") (pinfunction "2_2") (pintype "input"))
      (node (ref "C24") (pin "2") (pinfunction "2_2") (pintype "input"))
      (node (ref "C27") (pin "2") (pinfunction "2_2") (pintype "input"))
      (node (ref "C30") (pin "1") (pinfunction "1_1") (pintype "input"))
      (node (ref "C31") (pin "2") (pinfunction "2_2") (pintype "input"))
      (node (ref "C5") (pin "1") (pinfunction "1_1") (pintype "input"))
      (node (ref "C9") (pin "2") (pinfunction "2_2") (pintype "input"))
      (node (ref "CN1") (pin "1") (pinfunction "1_1") (pintype "unspecified"))
      (node (ref "I2C-AUX") (pin "2") (pinfunction "2_2") (pintype "unspecified"))
      (node (ref "L3") (pin "2") (pinfunction "2_2") (pintype "unspecified"))
      (node (ref "LD2410") (pin "5") (pinfunction "5_5") (pintype "unspecified"))
      (node (ref "LDO1") (pin "5") (pinfunction "VOUT_5") (pintype "unspecified"))
      (node (ref "MSM261S4030H0") (pin "2") (pinfunction "2_2") (pintype "unspecified"))
      (node (ref "R10") (pin "2") (pinfunction "2_2") (pintype "input"))
      (node (ref "R14") (pin "1") (pinfunction "1_1") (pintype "input"))
      (node (ref "R2") (pin "2") (pinfunction "2_2") (pintype "input"))
      (node (ref "R5") (pin "2") (pinfunction "2_2") (pintype "input"))
      (node (ref "R8") (pin "2") (pinfunction "2_2") (pintype "input"))
      (node (ref "U10") (pin "1") (pinfunction "VCC_1") (pintype "unspecified"))
      (node (ref "U3") (pin "1") (pinfunction "VIN_1") (pintype "unspecified"))
      (node (ref "U3") (pin "3") (pinfunction "CE_3") (pintype "unspecified"))
      (node (ref "U4") (pin "1") (pinfunction "VCC_1") (pintype "unspecified"))
      (node (ref "U6") (pin "1") (pinfunction "VIN_1") (pintype "unspecified"))
      (node (ref "U6") (pin "3") (pinfunction "CE_3") (pintype "unspecified"))
      (node (ref "U7") (pin "3") (pinfunction "3V3_3") (pintype "unspecified"))
      (node (ref "U8") (pin "2") (pinfunction "Vout_2") (pintype "unspecified"))
      (node (ref "U8") (pin "4") (pinfunction "Vout_4") (pintype "unspecified"))
    )
    (net (code "50") (name "VSYNC") (class "Default")
      (node (ref "FPC2") (pin "7") (pinfunction "7_7") (pintype "unspecified"))
      (node (ref "U7") (pin "16") (pinfunction "IO12_16") (pintype "unspecified"))
    )
    (net (code "51") (name "unconnected-(BOOT-B-Pad2)") (class "Default")
      (node (ref "BOOT") (pin "2") (pinfunction "B_2") (pintype "unspecified+no_connect"))
    )
    (net (code "52") (name "unconnected-(D5-Pad1)") (class "Default")
      (node (ref "D5") (pin "1") (pinfunction "1_1") (pintype "unspecified+no_connect"))
    )
    (net (code "53") (name "unconnected-(D5-Pad3)") (class "Default")
      (node (ref "D5") (pin "3") (pinfunction "3_3") (pintype "unspecified+no_connect"))
    )
    (net (code "54") (name "unconnected-(EN-B-Pad2)") (class "Default")
      (node (ref "EN") (pin "2") (pinfunction "B_2") (pintype "unspecified+no_connect"))
    )
    (net (code "55") (name "unconnected-(FPC2-Pad1)") (class "Default")
      (node (ref "FPC2") (pin "1") (pinfunction "1_1") (pintype "unspecified+no_connect"))
    )
    (net (code "56") (name "unconnected-(FPC2-Pad23)") (class "Default")
      (node (ref "FPC2") (pin "23") (pinfunction "23_23") (pintype "unspecified+no_connect"))
    )
    (net (code "57") (name "unconnected-(FPC2-Pad24)") (class "Default")
      (node (ref "FPC2") (pin "24") (pinfunction "24_24") (pintype "unspecified+no_connect"))
    )
    (net (code "58") (name "unconnected-(LDO1-NC-Pad4)") (class "Default")
      (node (ref "LDO1") (pin "4") (pinfunction "NC_4") (pintype "unspecified+no_connect"))
    )
    (net (code "59") (name "unconnected-(U2-CE-Pad3)") (class "Default")
      (node (ref "U2") (pin "3") (pinfunction "CE_3") (pintype "unspecified+no_connect"))
    )
    (net (code "60") (name "unconnected-(U2-NC-Pad4)") (class "Default")
      (node (ref "U2") (pin "4") (pinfunction "NC_4") (pintype "unspecified+no_connect"))
    )
    (net (code "61") (name "unconnected-(U2-VIN-Pad1)") (class "Default")
      (node (ref "U2") (pin "1") (pinfunction "VIN_1") (pintype "unspecified+no_connect"))
    )
    (net (code "62") (name "unconnected-(U2-VOUT-Pad5)") (class "Default")
      (node (ref "U2") (pin "5") (pinfunction "VOUT_5") (pintype "unspecified+no_connect"))
    )
    (net (code "63") (name "unconnected-(U2-VSS-Pad2)") (class "Default")
      (node (ref "U2") (pin "2") (pinfunction "VSS_2") (pintype "unspecified+no_connect"))
    )
    (net (code "64") (name "unconnected-(U3-NC-Pad4)") (class "Default")
      (node (ref "U3") (pin "4") (pinfunction "NC_4") (pintype "unspecified+no_connect"))
    )
    (net (code "65") (name "unconnected-(U6-NC-Pad4)") (class "Default")
      (node (ref "U6") (pin "4") (pinfunction "NC_4") (pintype "unspecified+no_connect"))
    )
    (net (code "66") (name "unconnected-(U7-IO26-Pad26)") (class "Default")
      (node (ref "U7") (pin "26") (pinfunction "IO26_26") (pintype "unspecified+no_connect"))
    )
    (net (code "67") (name "unconnected-(U7-IO40-Pad36)") (class "Default")
      (node (ref "U7") (pin "36") (pinfunction "IO40_36") (pintype "unspecified+no_connect"))
    )
    (net (code "68") (name "unconnected-(U7-IO41-Pad37)") (class "Default")
      (node (ref "U7") (pin "37") (pinfunction "IO41_37") (pintype "unspecified+no_connect"))
    )
    (net (code "69") (name "unconnected-(U7-IO42-Pad38)") (class "Default")
      (node (ref "U7") (pin "38") (pinfunction "IO42_38") (pintype "unspecified+no_connect"))
    )
    (net (code "70") (name "unconnected-(U7-IO45-Pad41)") (class "Default")
      (node (ref "U7") (pin "41") (pinfunction "IO45_41") (pintype "unspecified+no_connect"))
    )
    (net (code "71") (name "unconnected-(U7-IO46-Pad44)") (class "Default")
      (node (ref "U7") (pin "44") (pinfunction "IO46_44") (pintype "unspecified+no_connect"))
    )
    (net (code "72") (name "unconnected-(U7-IO47-Pad27)") (class "Default")
      (node (ref "U7") (pin "27") (pinfunction "IO47_27") (pintype "unspecified+no_connect"))
    )
    (net (code "73") (name "unconnected-(U7-IO48-Pad30)") (class "Default")
      (node (ref "U7") (pin "30") (pinfunction "IO48_30") (pintype "unspecified+no_connect"))
    )
    (net (code "74") (name "unconnected-(U7-RXD0-Pad40)") (class "Default")
      (node (ref "U7") (pin "40") (pinfunction "RXD0_40") (pintype "unspecified+no_connect"))
    )
    (net (code "75") (name "unconnected-(U7-TXD0-Pad39)") (class "Default")
      (node (ref "U7") (pin "39") (pinfunction "TXD0_39") (pintype "unspecified+no_connect"))
    )
    (net (code "76") (name "unconnected-(USBC1-SBU1-PadA8)") (class "Default")
      (node (ref "USBC1") (pin "A8") (pinfunction "SBU1_A8") (pintype "unspecified+no_connect"))
    )
    (net (code "77") (name "unconnected-(USBC1-SBU2-PadB8)") (class "Default")
      (node (ref "USBC1") (pin "B8") (pinfunction "SBU2_B8") (pintype "unspecified+no_connect"))
    )
  )
)
